# isoSPI_Interface.net
KiCad netlist of a schematic drawn in Altium Designer
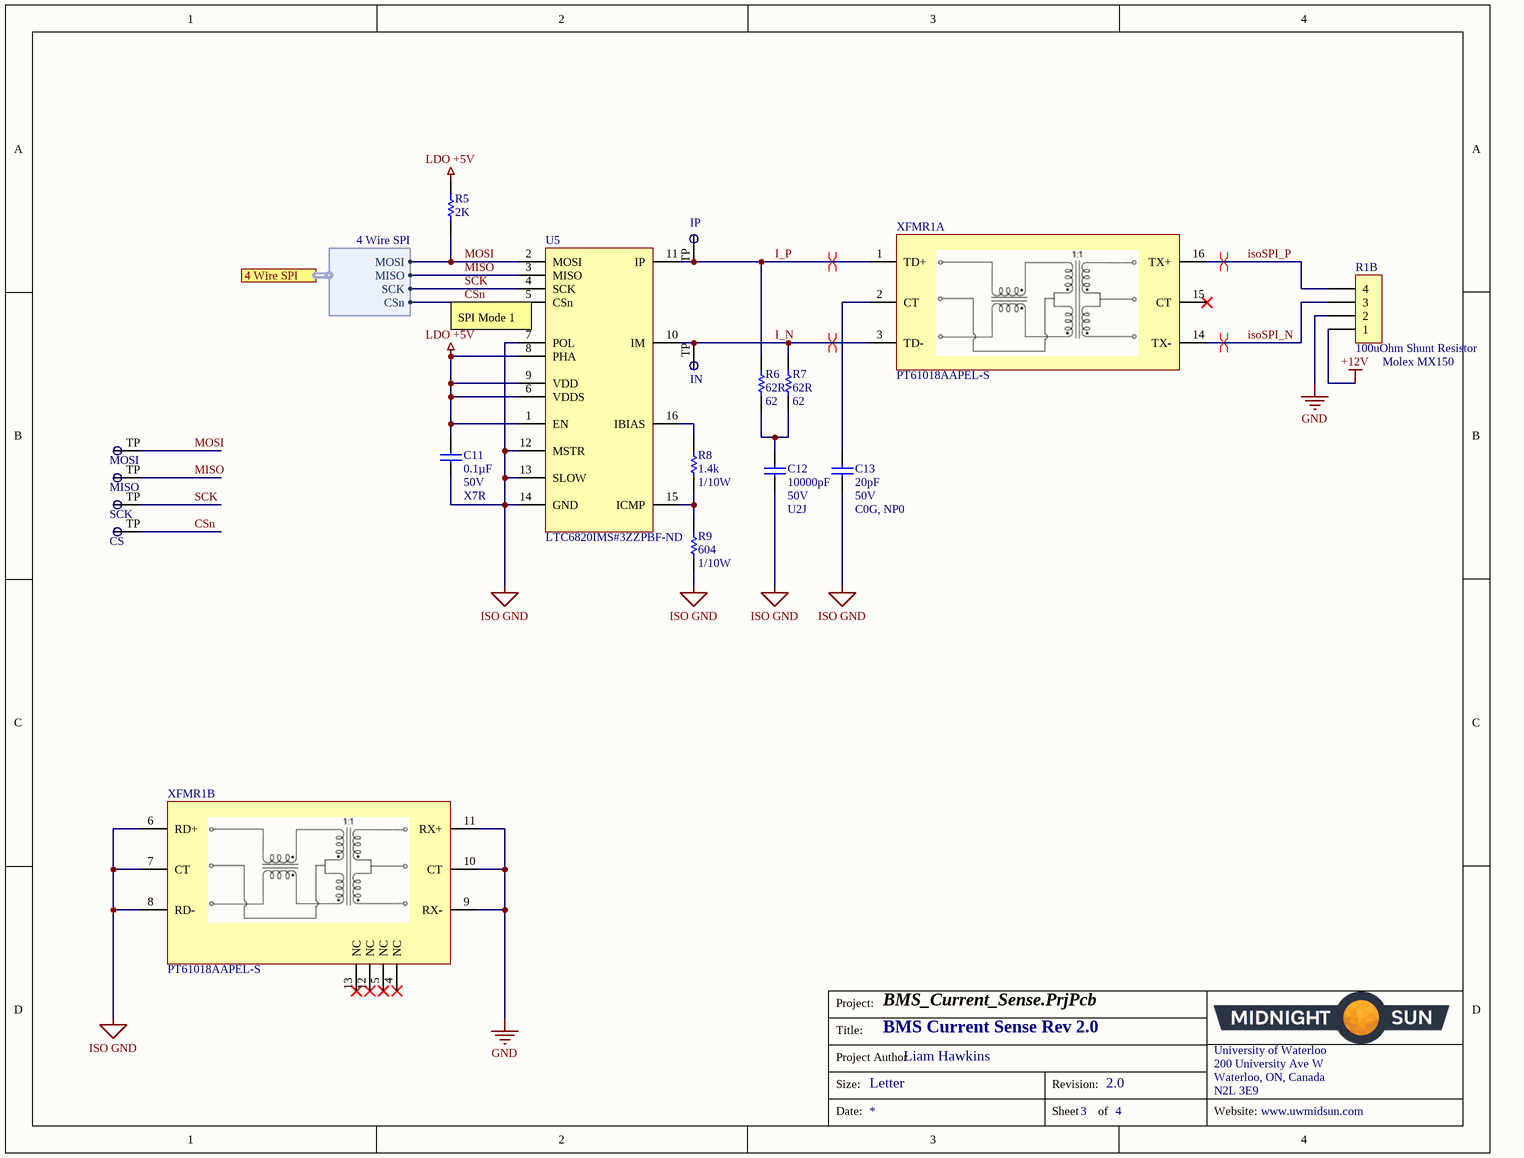
[diagram p0: isoSPI_Interface.SchDoc]

(export (version "E")
  (design (tool "Eeschema 10.0.6"))
  (components
    (comp (ref "C11")
      (value "CAP CER 0.1UF 50V 10% X7R 0603")
      (footprint "CAP, 0603")
      (description "0.10µF ±10% 50V Ceramic Capacitor X7R 0603 (1608 Metric)")
      (fields
        (field (name "TOLERANCE") "±10%")
        (field (name "CAPACITANCE") "0.1µF")
        (field (name "VOLTAGE") "50V")
        (field (name "TEMPERATURE COEFFICIENT") "X7R")
      )
      (libsource (lib "Schematic Diagrams") (part "CAP CER 0.1UF 50V 10% X7R 0603"))
    )
    (comp (ref "C12")
      (value "CAP CER 10nF 50V 5% X7R 0603")
      (footprint "CAP, 0603")
      (description "10000pF ±5% 50V Ceramic Capacitor U2J 0603 (1608 Metric)")
      (fields
        (field (name "TOLERANCE") "±5%")
        (field (name "CAPACITANCE") "10000pF")
        (field (name "VOLTAGE") "50V")
        (field (name "TEMPERATURE COEFFICIENT") "U2J")
      )
      (libsource (lib "Schematic Diagrams") (part "CAP CER 10nF 50V 5% X7R 0603"))
    )
    (comp (ref "C13")
      (value "CAP CER 20PF 50V ±5% C0G/NP0 0603")
      (footprint "CAP, 0603")
      (description "20pF ±5% 50V Ceramic Capacitor C0G, NP0 0603 (1608 Metric)")
      (fields
        (field (name "TOLERANCE") "±5%")
        (field (name "CAPACITANCE") "20pF")
        (field (name "VOLTAGE") "50V")
        (field (name "TEMPERATURE COEFFICIENT") "C0G, NP0")
      )
      (libsource (lib "Schematic Diagrams") (part "CAP CER 20PF 50V ±5% C0G/NP0 0603"))
    )
    (comp (ref "CS")
      (value "Test Point")
      (footprint "Test Point")
      (libsource (lib "Schematic Diagrams") (part "Test Point"))
    )
    (comp (ref "IN")
      (value "Test Point")
      (footprint "Test Point")
      (libsource (lib "Schematic Diagrams") (part "Test Point"))
    )
    (comp (ref "IP")
      (value "Test Point")
      (footprint "Test Point")
      (libsource (lib "Schematic Diagrams") (part "Test Point"))
    )
    (comp (ref "MISO")
      (value "Test Point")
      (footprint "Test Point")
      (libsource (lib "Schematic Diagrams") (part "Test Point"))
    )
    (comp (ref "MOSI")
      (value "Test Point")
      (footprint "Test Point")
      (libsource (lib "Schematic Diagrams") (part "Test Point"))
    )
    (comp (ref "R1")
      (value "100uOhm Shunt Resistor")
      (footprint "RES SHUNT 100UOHM 60MM")
      (fields (field (name "TOLERANCE") "±5%"))
      (libsource (lib "Schematic Diagrams") (part "RES SHUNT 100UOHM 5% 36W 60MM"))
    )
    (comp (ref "R5")
      (value "2K")
      (footprint "RES, 0603")
      (description "2k Ohm ±1% 0.1W, 1/10W Chip Resistor 0603 (1608 Metric) Moisture Resistant Thick Film")
      (fields
        (field (name "MANUFACTURER") "Yageo")
        (field (name "MANUFACTURER PART NUMBER") "RC0603FR-072KL")
      )
      (libsource (lib "Schematic Diagrams") (part "RES 2K OHM 1% 1/10W 0603"))
    )
    (comp (ref "R6")
      (value "62R")
      (footprint "RES, 0603")
      (description "62 Ohms ±0.1% 0.1W, 1/10W Chip Resistor 0603 (1608 Metric) Automotive AEC-Q200 Thin Film")
      (fields
        (field (name "MANUFACTURER") "Panasonic Electronic Components")
        (field (name "MANUFACTURER PART NUMBER") "ERA-3AEB620V")
        (field (name "ALTIUM_VALUE") "62")
      )
      (libsource (lib "Schematic Diagrams") (part "RES 62 OHM 0.1% 1/10W 0603"))
    )
    (comp (ref "R7")
      (value "62R")
      (footprint "RES, 0603")
      (description "62 Ohms ±0.1% 0.1W, 1/10W Chip Resistor 0603 (1608 Metric) Automotive AEC-Q200 Thin Film")
      (fields
        (field (name "MANUFACTURER") "Panasonic Electronic Components")
        (field (name "MANUFACTURER PART NUMBER") "ERA-3AEB620V")
        (field (name "ALTIUM_VALUE") "62")
      )
      (libsource (lib "Schematic Diagrams") (part "RES 62 OHM 0.1% 1/10W 0603"))
    )
    (comp (ref "R8")
      (value "RES 1.4k OHM 1% 1/10W 0603")
      (footprint "RES, 0603")
      (description "RES SMD 1.4K OHM 1% 1/10W 0603")
      (fields
        (field (name "TOLERANCE") "±1%")
        (field (name "RESISTANCE") "1.4k")
        (field (name "POWER") "1/10W")
      )
      (libsource (lib "Schematic Diagrams") (part "RES 1.4k OHM 1% 1/10W 0603"))
    )
    (comp (ref "R9")
      (value "RES 604 OHM 1% 1/10W 0603")
      (footprint "RES, 0603")
      (description "RES SMD 604 OHM 1% 1/10W 0603")
      (fields
        (field (name "TOLERANCE") "±1%")
        (field (name "RESISTANCE") "604")
        (field (name "POWER") "1/10W")
      )
      (libsource (lib "Schematic Diagrams") (part "RES 604 OHM 1% 1/10W 0603"))
    )
    (comp (ref "SCK")
      (value "Test Point")
      (footprint "Test Point")
      (libsource (lib "Schematic Diagrams") (part "Test Point"))
    )
    (comp (ref "U5")
      (value "IC ISOSPI COMM INTERFACE LTC6820IMS#3ZZPBF")
      (footprint "IC isoSPI Interface LTC6820 MSOP")
      (description "Isolated Communications Interface Interface 16-MSOP")
      (fields
        (field (name "MANUFACTURER") "Linear Technology")
        (field (name "MANUFACTURER PART NUMBER") "LTC6820IMS#3ZZPBF")
        (field (name "SUPPLIER PART NUMBER 1") "LTC6820IMS#3ZZPBF-ND")
      )
      (libsource (lib "Schematic Diagrams") (part "IC ISOSPI COMM INTERFACE LTC6820IMS#3ZZPBF"))
    )
    (comp (ref "XFMR1")
      (value "IC PULSE XFMR 1CT:1CT 350UH SMD")
      (footprint "IC, PULSE XFMR 1CT:1CT 350UH SMD")
      (description "PULSE XFMR 1CT:1CT 350UH SMD")
      (fields (field (name "MANUFACTURER") "Bourns Inc.") (field (name "MFG_PN") "PT61018AAPEL-S"))
      (libsource (lib "Schematic Diagrams") (part "IC PULSE XFMR 1CT{colon}1CT 350UH SMD"))
    )
  )
  (nets
    (net (code "4") (name "+12V") (class "Default")
      (node (ref "R1") (pin "1") (pinfunction "1_1") (pintype "passive"))
    )
    (net (code "5") (name "/CSn") (class "Default")
      (node (ref "CS") (pin "TP") (pinfunction "1_TP") (pintype "passive"))
      (node (ref "U5") (pin "5") (pinfunction "CSn_5") (pintype "passive"))
    )
    (net (code "6") (name "/I_N") (class "Default")
      (node (ref "IN") (pin "TP") (pinfunction "1_TP") (pintype "passive"))
      (node (ref "R7") (pin "1") (pinfunction "1_1") (pintype "passive"))
      (node (ref "U5") (pin "10") (pinfunction "IM_10") (pintype "passive"))
      (node (ref "XFMR1") (pin "3") (pinfunction "TD-_3") (pintype "passive"))
    )
    (net (code "7") (name "/I_P") (class "Default")
      (node (ref "IP") (pin "TP") (pinfunction "1_TP") (pintype "passive"))
      (node (ref "R6") (pin "1") (pinfunction "1_1") (pintype "passive"))
      (node (ref "U5") (pin "11") (pinfunction "IP_11") (pintype "passive"))
      (node (ref "XFMR1") (pin "1") (pinfunction "TD+_1") (pintype "passive"))
    )
    (net (code "8") (name "/MISO") (class "Default")
      (node (ref "MISO") (pin "TP") (pinfunction "1_TP") (pintype "passive"))
      (node (ref "U5") (pin "3") (pinfunction "MISO_3") (pintype "passive"))
    )
    (net (code "9") (name "/MOSI") (class "Default")
      (node (ref "MOSI") (pin "TP") (pinfunction "1_TP") (pintype "passive"))
      (node (ref "R5") (pin "2") (pinfunction "2_2") (pintype "passive"))
      (node (ref "U5") (pin "2") (pinfunction "MOSI_2") (pintype "passive"))
    )
    (net (code "10") (name "/SCK") (class "Default")
      (node (ref "SCK") (pin "TP") (pinfunction "1_TP") (pintype "passive"))
      (node (ref "U5") (pin "4") (pinfunction "SCK_4") (pintype "passive"))
    )
    (net (code "11") (name "/isoSPI_N") (class "Default")
      (node (ref "R1") (pin "3") (pinfunction "3_3") (pintype "passive"))
      (node (ref "XFMR1") (pin "14") (pinfunction "TX-_14") (pintype "passive"))
    )
    (net (code "12") (name "/isoSPI_P") (class "Default")
      (node (ref "R1") (pin "4") (pinfunction "4_4") (pintype "passive"))
      (node (ref "XFMR1") (pin "16") (pinfunction "TX+_16") (pintype "passive"))
    )
    (net (code "14") (name "GND") (class "Default")
      (node (ref "R1") (pin "2") (pinfunction "2_2") (pintype "passive"))
      (node (ref "XFMR1") (pin "10") (pinfunction "CT_10") (pintype "passive"))
      (node (ref "XFMR1") (pin "11") (pinfunction "RX+_11") (pintype "passive"))
      (node (ref "XFMR1") (pin "9") (pinfunction "RX-_9") (pintype "passive"))
    )
    (net (code "15") (name "ISO GND") (class "Default")
      (node (ref "C11") (pin "2") (pinfunction "2_2") (pintype "passive"))
      (node (ref "C12") (pin "2") (pinfunction "2_2") (pintype "passive"))
      (node (ref "C13") (pin "2") (pinfunction "2_2") (pintype "passive"))
      (node (ref "R9") (pin "2") (pinfunction "2_2") (pintype "passive"))
      (node (ref "U5") (pin "12") (pinfunction "MSTR_12") (pintype "passive"))
      (node (ref "U5") (pin "13") (pinfunction "SLOW_13") (pintype "passive"))
      (node (ref "U5") (pin "14") (pinfunction "GND_14") (pintype "passive"))
      (node (ref "U5") (pin "7") (pinfunction "POL_7") (pintype "passive"))
      (node (ref "XFMR1") (pin "6") (pinfunction "RD+_6") (pintype "passive"))
      (node (ref "XFMR1") (pin "7") (pinfunction "CT_7") (pintype "passive"))
      (node (ref "XFMR1") (pin "8") (pinfunction "RD-_8") (pintype "passive"))
    )
    (net (code "16") (name "LDO +5V") (class "Default")
      (node (ref "C11") (pin "1") (pinfunction "1_1") (pintype "passive"))
      (node (ref "R5") (pin "1") (pinfunction "1_1") (pintype "passive"))
      (node (ref "U5") (pin "1") (pinfunction "EN_1") (pintype "passive"))
      (node (ref "U5") (pin "6") (pinfunction "VDDS_6") (pintype "passive"))
      (node (ref "U5") (pin "8") (pinfunction "PHA_8") (pintype "passive"))
      (node (ref "U5") (pin "9") (pinfunction "VDD_9") (pintype "passive"))
    )
    (net (code "17") (name "Net-(C12-Pad1)") (class "Default")
      (node (ref "C12") (pin "1") (pinfunction "1_1") (pintype "passive"))
      (node (ref "R6") (pin "2") (pinfunction "2_2") (pintype "passive"))
      (node (ref "R7") (pin "2") (pinfunction "2_2") (pintype "passive"))
    )
    (net (code "18") (name "Net-(C13-Pad1)") (class "Default")
      (node (ref "C13") (pin "1") (pinfunction "1_1") (pintype "passive"))
      (node (ref "XFMR1") (pin "2") (pinfunction "CT_2") (pintype "passive"))
    )
    (net (code "19") (name "Net-(U5-IBIAS)") (class "Default")
      (node (ref "R8") (pin "1") (pinfunction "1_1") (pintype "passive"))
      (node (ref "U5") (pin "16") (pinfunction "IBIAS_16") (pintype "passive"))
    )
    (net (code "20") (name "Net-(U5-ICMP)") (class "Default")
      (node (ref "R8") (pin "2") (pinfunction "2_2") (pintype "passive"))
      (node (ref "R9") (pin "1") (pinfunction "1_1") (pintype "passive"))
      (node (ref "U5") (pin "15") (pinfunction "ICMP_15") (pintype "passive"))
    )
    (net (code "21") (name "unconnected-(XFMR1A-CT-Pad15)") (class "Default")
      (node (ref "XFMR1") (pin "15") (pinfunction "CT_15") (pintype "passive+no_connect"))
    )
    (net (code "22") (name "unconnected-(XFMR1B-NC-Pad4)") (class "Default")
      (node (ref "XFMR1") (pin "4") (pinfunction "NC_4") (pintype "passive+no_connect"))
    )
    (net (code "23") (name "unconnected-(XFMR1B-NC-Pad5)") (class "Default")
      (node (ref "XFMR1") (pin "5") (pinfunction "NC_5") (pintype "passive+no_connect"))
    )
    (net (code "24") (name "unconnected-(XFMR1B-NC-Pad12)") (class "Default")
      (node (ref "XFMR1") (pin "12") (pinfunction "NC_12") (pintype "passive+no_connect"))
    )
    (net (code "25") (name "unconnected-(XFMR1B-NC-Pad13)") (class "Default")
      (node (ref "XFMR1") (pin "13") (pinfunction "NC_13") (pintype "passive+no_connect"))
    )
  )
)
